# Uno.net
KiCad netlist of a schematic drawn in EAGLE
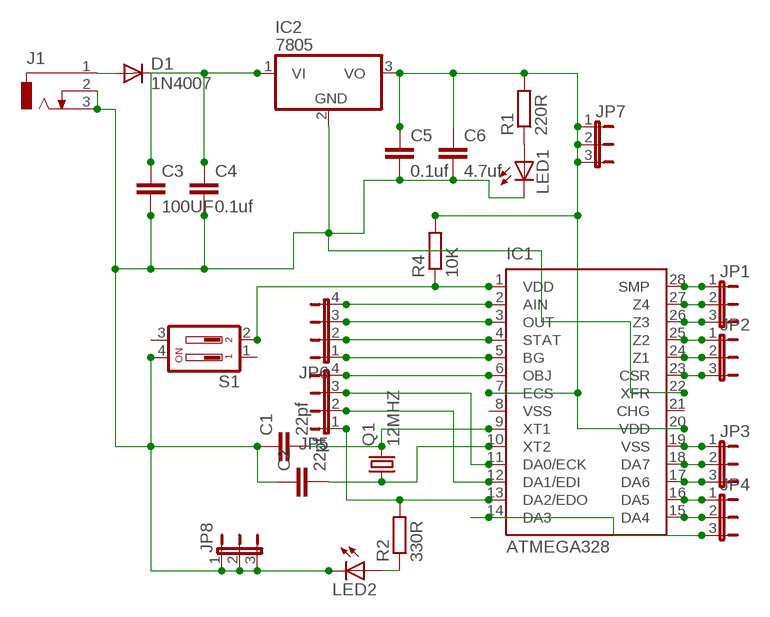
[diagram p0: schematic, sheet 1]

(export (version "E")
  (design (tool "Eeschema 10.0.6"))
  (components
    (comp (ref "C1")
      (value "22pf")
      (footprint "eagle-import:C2.5-2")
      (libsource (lib "eagle-import") (part "C2.5/2"))
    )
    (comp (ref "C2")
      (value "22pf")
      (footprint "eagle-import:C2.5-2")
      (libsource (lib "eagle-import") (part "C2.5/2"))
    )
    (comp (ref "C3")
      (value "100UF")
      (footprint "eagle-import:C2.5-2")
      (libsource (lib "eagle-import") (part "C2.5/2"))
    )
    (comp (ref "C4")
      (value "0.1uf")
      (footprint "eagle-import:C2.5-2")
      (libsource (lib "eagle-import") (part "C2.5/2"))
    )
    (comp (ref "C5")
      (value "0.1uf")
      (footprint "eagle-import:C2.5-2")
      (libsource (lib "eagle-import") (part "C2.5/2"))
    )
    (comp (ref "C6")
      (value "4.7uf")
      (footprint "eagle-import:C2.5-2")
      (libsource (lib "eagle-import") (part "C2.5/2"))
    )
    (comp (ref "D1")
      (value "1N4007")
      (footprint "eagle-import:DO41-10")
      (libsource (lib "eagle-import") (part "1N4004"))
    )
    (comp (ref "IC1")
      (value "ATMEGA328")
      (footprint "eagle-import:DIL28-3")
      (libsource (lib "eagle-import") (part "QT9701BD"))
    )
    (comp (ref "IC2")
      (value "7805")
      (footprint "eagle-import:TO220V")
      (libsource (lib "eagle-import") (part "78TV6"))
    )
    (comp (ref "J1")
      (value "DCJ0303")
      (footprint "eagle-import:DCJ0303")
      (libsource (lib "eagle-import") (part "DCJ0303"))
    )
    (comp (ref "JP1")
      (value "JP2E")
      (footprint "eagle-import:JP2")
      (libsource (lib "eagle-import") (part "JP2E"))
    )
    (comp (ref "JP2")
      (value "JP2E")
      (footprint "eagle-import:JP2")
      (libsource (lib "eagle-import") (part "JP2E"))
    )
    (comp (ref "JP3")
      (value "JP2E")
      (footprint "eagle-import:JP2")
      (libsource (lib "eagle-import") (part "JP2E"))
    )
    (comp (ref "JP4")
      (value "JP2E")
      (footprint "eagle-import:JP2")
      (libsource (lib "eagle-import") (part "JP2E"))
    )
    (comp (ref "JP5")
      (value "JP4E")
      (footprint "eagle-import:JP4")
      (libsource (lib "eagle-import") (part "JP4E"))
    )
    (comp (ref "JP6")
      (value "JP4E")
      (footprint "eagle-import:JP4")
      (libsource (lib "eagle-import") (part "JP4E"))
    )
    (comp (ref "JP7")
      (value "JP2E")
      (footprint "eagle-import:JP2")
      (libsource (lib "eagle-import") (part "JP2E"))
    )
    (comp (ref "JP8")
      (value "JP2E")
      (footprint "eagle-import:JP2")
      (libsource (lib "eagle-import") (part "JP2E"))
    )
    (comp (ref "LED1")
      (value "LED3MM")
      (footprint "eagle-import:LED3MM")
      (libsource (lib "eagle-import") (part "LED3MM"))
    )
    (comp (ref "LED2")
      (value "LED3MM")
      (footprint "eagle-import:LED3MM")
      (libsource (lib "eagle-import") (part "LED3MM"))
    )
    (comp (ref "Q1")
      (value "12MHZ")
      (footprint "eagle-import:HC49_S")
      (libsource (lib "eagle-import") (part "CRYSTALHC49S"))
    )
    (comp (ref "R1")
      (value "220R")
      (footprint "eagle-import:0207_10")
      (libsource (lib "eagle-import") (part "R-EU_0207/10"))
    )
    (comp (ref "R2")
      (value "330R")
      (footprint "eagle-import:0207_10")
      (libsource (lib "eagle-import") (part "R-EU_0207/10"))
    )
    (comp (ref "R4")
      (value "10K")
      (footprint "eagle-import:0207_10")
      (libsource (lib "eagle-import") (part "R-EU_0207/10"))
    )
    (comp (ref "S1")
      (value "DP02")
      (footprint "eagle-import:DP-02")
      (fields (field (name "MPN") "MCDP02"))
      (libsource (lib "eagle-import") (part "DP02"))
    )
  )
  (nets
    (net (code "1") (name "Net-(D1-PadA)") (class "Default")
      (node (ref "D1") (pin "A") (pinfunction "A_A") (pintype "passive"))
      (node (ref "J1") (pin "1") (pinfunction "1_1") (pintype "passive"))
    )
    (net (code "2") (name "Net-(IC1-AIN)") (class "Default")
      (node (ref "IC1") (pin "2") (pinfunction "AIN_2") (pintype "input"))
      (node (ref "JP6") (pin "4") (pinfunction "4_4") (pintype "passive"))
    )
    (net (code "3") (name "Net-(IC1-BG)") (class "Default")
      (node (ref "IC1") (pin "5") (pinfunction "BG_5") (pintype "input"))
      (node (ref "JP6") (pin "1") (pinfunction "1_1") (pintype "passive"))
    )
    (net (code "4") (name "Net-(IC1-CSR)") (class "Default")
      (node (ref "IC1") (pin "23") (pinfunction "CSR_23") (pintype "output"))
      (node (ref "JP2") (pin "3") (pinfunction "3_3") (pintype "passive"))
    )
    (net (code "5") (name "Net-(IC1-DA0{slash}ECK)") (class "Default")
      (node (ref "IC1") (pin "11") (pinfunction "DA0/ECK_11") (pintype "output"))
      (node (ref "JP5") (pin "3") (pinfunction "3_3") (pintype "passive"))
    )
    (net (code "6") (name "Net-(IC1-DA1{slash}EDI)") (class "Default")
      (node (ref "IC1") (pin "12") (pinfunction "DA1/EDI_12") (pintype "output"))
      (node (ref "JP5") (pin "2") (pinfunction "2_2") (pintype "passive"))
    )
    (net (code "7") (name "Net-(IC1-DA2{slash}EDO)") (class "Default")
      (node (ref "IC1") (pin "13") (pinfunction "DA2/EDO_13") (pintype "output"))
      (node (ref "JP5") (pin "1") (pinfunction "1_1") (pintype "passive"))
      (node (ref "R2") (pin "2") (pinfunction "2_2") (pintype "passive"))
    )
    (net (code "8") (name "Net-(IC1-DA3)") (class "Default")
      (node (ref "IC1") (pin "14") (pinfunction "DA3_14") (pintype "output"))
      (node (ref "JP4") (pin "3") (pinfunction "3_3") (pintype "passive"))
    )
    (net (code "9") (name "Net-(IC1-DA4)") (class "Default")
      (node (ref "IC1") (pin "15") (pinfunction "DA4_15") (pintype "output"))
      (node (ref "JP4") (pin "2") (pinfunction "2_2") (pintype "passive"))
    )
    (net (code "10") (name "Net-(IC1-DA5)") (class "Default")
      (node (ref "IC1") (pin "16") (pinfunction "DA5_16") (pintype "output"))
      (node (ref "JP4") (pin "1") (pinfunction "1_1") (pintype "passive"))
    )
    (net (code "11") (name "Net-(IC1-DA6)") (class "Default")
      (node (ref "IC1") (pin "17") (pinfunction "DA6_17") (pintype "output"))
      (node (ref "JP3") (pin "3") (pinfunction "3_3") (pintype "passive"))
    )
    (net (code "12") (name "Net-(IC1-DA7)") (class "Default")
      (node (ref "IC1") (pin "18") (pinfunction "DA7_18") (pintype "output"))
      (node (ref "JP3") (pin "2") (pinfunction "2_2") (pintype "passive"))
    )
    (net (code "13") (name "Net-(IC1-ECS)") (class "Default")
      (node (ref "C5") (pin "1") (pinfunction "1_1") (pintype "passive"))
      (node (ref "C6") (pin "1") (pinfunction "1_1") (pintype "passive"))
      (node (ref "IC1") (pin "20") (pinfunction "VDD_20") (pintype "input"))
      (node (ref "IC1") (pin "7") (pinfunction "ECS_7") (pintype "output"))
      (node (ref "IC2") (pin "3") (pinfunction "VO_3") (pintype "passive"))
      (node (ref "JP7") (pin "1") (pinfunction "1_1") (pintype "passive"))
      (node (ref "JP7") (pin "2") (pinfunction "2_2") (pintype "passive"))
      (node (ref "JP7") (pin "3") (pinfunction "3_3") (pintype "passive"))
      (node (ref "R1") (pin "2") (pinfunction "2_2") (pintype "passive"))
      (node (ref "R4") (pin "2") (pinfunction "2_2") (pintype "passive"))
    )
    (net (code "14") (name "Net-(IC1-OBJ)") (class "Default")
      (node (ref "IC1") (pin "6") (pinfunction "OBJ_6") (pintype "input"))
      (node (ref "JP5") (pin "4") (pinfunction "4_4") (pintype "passive"))
    )
    (net (code "15") (name "Net-(IC1-OUT)") (class "Default")
      (node (ref "IC1") (pin "3") (pinfunction "OUT_3") (pintype "output"))
      (node (ref "JP6") (pin "3") (pinfunction "3_3") (pintype "passive"))
    )
    (net (code "16") (name "Net-(IC1-SMP)") (class "Default")
      (node (ref "IC1") (pin "28") (pinfunction "SMP_28") (pintype "output"))
      (node (ref "JP1") (pin "1") (pinfunction "1_1") (pintype "passive"))
    )
    (net (code "17") (name "Net-(IC1-STAT)") (class "Default")
      (node (ref "IC1") (pin "4") (pinfunction "STAT_4") (pintype "output"))
      (node (ref "JP6") (pin "2") (pinfunction "2_2") (pintype "passive"))
    )
    (net (code "18") (name "Net-(IC1-VDD-Pad1)") (class "Default")
      (node (ref "IC1") (pin "1") (pinfunction "VDD_1") (pintype "input"))
      (node (ref "R4") (pin "1") (pinfunction "1_1") (pintype "passive"))
      (node (ref "S1") (pin "2") (pinfunction "2_2") (pintype "passive"))
    )
    (net (code "19") (name "Net-(IC1-VSS-Pad19)") (class "Default")
      (node (ref "IC1") (pin "19") (pinfunction "VSS_19") (pintype "input"))
      (node (ref "JP3") (pin "1") (pinfunction "1_1") (pintype "passive"))
    )
    (net (code "20") (name "Net-(IC1-XFR)") (class "Default")
      (node (ref "C1") (pin "1") (pinfunction "1_1") (pintype "passive"))
      (node (ref "C2") (pin "1") (pinfunction "1_1") (pintype "passive"))
      (node (ref "C3") (pin "2") (pinfunction "2_2") (pintype "passive"))
      (node (ref "C4") (pin "2") (pinfunction "2_2") (pintype "passive"))
      (node (ref "C5") (pin "2") (pinfunction "2_2") (pintype "passive"))
      (node (ref "C6") (pin "2") (pinfunction "2_2") (pintype "passive"))
      (node (ref "IC1") (pin "22") (pinfunction "XFR_22") (pintype "output"))
      (node (ref "IC2") (pin "2") (pinfunction "GND_2") (pintype "passive"))
      (node (ref "J1") (pin "2") (pinfunction "2_2") (pintype "passive"))
      (node (ref "J1") (pin "3") (pinfunction "3_3") (pintype "passive"))
      (node (ref "JP8") (pin "1") (pinfunction "1_1") (pintype "passive"))
      (node (ref "JP8") (pin "2") (pinfunction "2_2") (pintype "passive"))
      (node (ref "JP8") (pin "3") (pinfunction "3_3") (pintype "passive"))
      (node (ref "LED1") (pin "K") (pinfunction "C_K") (pintype "passive"))
      (node (ref "LED2") (pin "K") (pinfunction "C_K") (pintype "passive"))
      (node (ref "S1") (pin "4") (pinfunction "4_4") (pintype "passive"))
    )
    (net (code "21") (name "Net-(IC1-XT1)") (class "Default")
      (node (ref "C1") (pin "2") (pinfunction "2_2") (pintype "passive"))
      (node (ref "IC1") (pin "9") (pinfunction "XT1_9") (pintype "input"))
      (node (ref "Q1") (pin "2") (pinfunction "2_2") (pintype "passive"))
    )
    (net (code "22") (name "Net-(IC1-XT2)") (class "Default")
      (node (ref "C2") (pin "2") (pinfunction "2_2") (pintype "passive"))
      (node (ref "IC1") (pin "10") (pinfunction "XT2_10") (pintype "output"))
      (node (ref "Q1") (pin "1") (pinfunction "1_1") (pintype "passive"))
    )
    (net (code "23") (name "Net-(IC1-Z1)") (class "Default")
      (node (ref "IC1") (pin "24") (pinfunction "Z1_24") (pintype "output"))
      (node (ref "JP2") (pin "2") (pinfunction "2_2") (pintype "passive"))
    )
    (net (code "24") (name "Net-(IC1-Z2)") (class "Default")
      (node (ref "IC1") (pin "25") (pinfunction "Z2_25") (pintype "output"))
      (node (ref "JP2") (pin "1") (pinfunction "1_1") (pintype "passive"))
    )
    (net (code "25") (name "Net-(IC1-Z3)") (class "Default")
      (node (ref "IC1") (pin "26") (pinfunction "Z3_26") (pintype "output"))
      (node (ref "JP1") (pin "3") (pinfunction "3_3") (pintype "passive"))
    )
    (net (code "26") (name "Net-(IC1-Z4)") (class "Default")
      (node (ref "IC1") (pin "27") (pinfunction "Z4_27") (pintype "output"))
      (node (ref "JP1") (pin "2") (pinfunction "2_2") (pintype "passive"))
    )
    (net (code "27") (name "Net-(IC2-VI)") (class "Default")
      (node (ref "C3") (pin "1") (pinfunction "1_1") (pintype "passive"))
      (node (ref "C4") (pin "1") (pinfunction "1_1") (pintype "passive"))
      (node (ref "D1") (pin "C") (pinfunction "C_C") (pintype "passive"))
      (node (ref "IC2") (pin "1") (pinfunction "VI_1") (pintype "input"))
    )
    (net (code "28") (name "Net-(LED1-PadA)") (class "Default")
      (node (ref "LED1") (pin "A") (pinfunction "A_A") (pintype "passive"))
      (node (ref "R1") (pin "1") (pinfunction "1_1") (pintype "passive"))
    )
    (net (code "29") (name "Net-(LED2-PadA)") (class "Default")
      (node (ref "LED2") (pin "A") (pinfunction "A_A") (pintype "passive"))
      (node (ref "R2") (pin "1") (pinfunction "1_1") (pintype "passive"))
    )
    (net (code "30") (name "unconnected-(IC1-CHG-Pad21)") (class "Default")
      (node (ref "IC1") (pin "21") (pinfunction "CHG_21") (pintype "output"))
    )
    (net (code "31") (name "unconnected-(IC1-VSS-Pad8)") (class "Default")
      (node (ref "IC1") (pin "8") (pinfunction "VSS_8") (pintype "input"))
    )
    (net (code "32") (name "unconnected-(S1-Pad1)") (class "Default")
      (node (ref "S1") (pin "1") (pinfunction "1_1") (pintype "passive"))
    )
    (net (code "33") (name "unconnected-(S1-Pad3)") (class "Default")
      (node (ref "S1") (pin "3") (pinfunction "3_3") (pintype "passive"))
    )
  )
)
